# GPS.net
KiCad netlist of a schematic drawn in Altium Designer
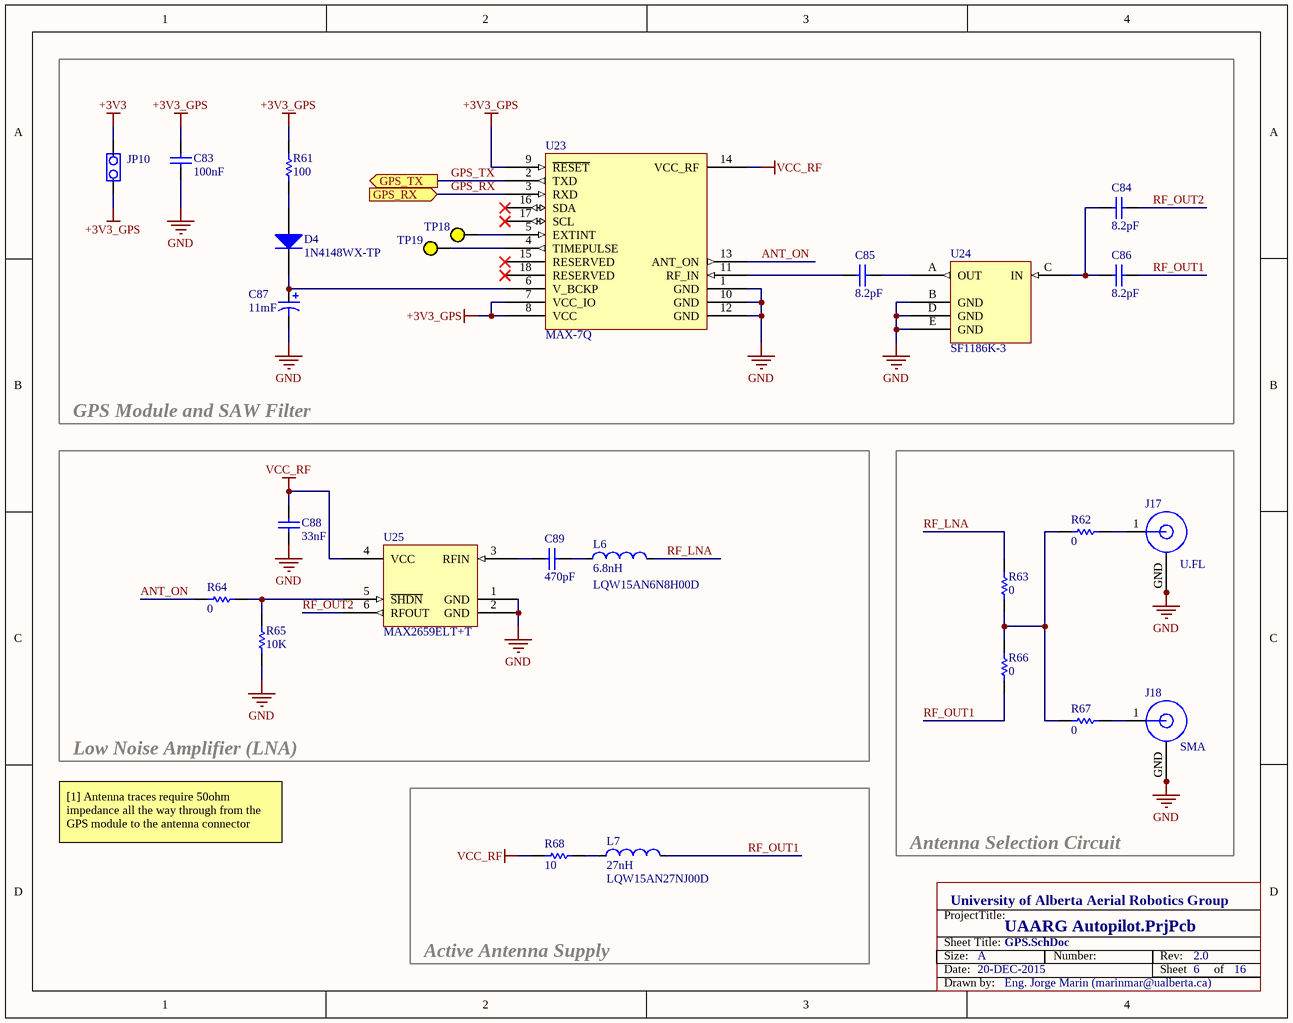
[diagram p0: GPS.SchDoc]

(export (version "E")
  (design (tool "Eeschema 10.0.6"))
  (components
    (comp (ref "C83")
      (value "100nF")
      (footprint "CAP_0402[1005M]")
      (description "Capacitor")
      (fields
        (field (name "MANUFACTURER") "Yageo")
        (field (name "MANUFACTURER PART NUMBER") "CC0402KRX7R6BB104")
      )
      (libsource (lib "UAARG Autopilot") (part "CAP"))
    )
    (comp (ref "C84")
      (value "8.2pF")
      (footprint "CAP_0402[1005M]")
      (description "Capacitor")
      (fields
        (field (name "MANUFACTURER") "Yageo")
        (field (name "MANUFACTURER PART NUMBER") "CC0402BRNPO9BN8R2")
      )
      (libsource (lib "UAARG Autopilot") (part "CAP"))
    )
    (comp (ref "C85")
      (value "8.2pF")
      (footprint "CAP_0402[1005M]")
      (description "Capacitor")
      (fields
        (field (name "MANUFACTURER") "Yageo")
        (field (name "MANUFACTURER PART NUMBER") "CC0402BRNPO9BN8R2")
      )
      (libsource (lib "UAARG Autopilot") (part "CAP"))
    )
    (comp (ref "C86")
      (value "8.2pF")
      (footprint "CAP_0402[1005M]")
      (description "Capacitor")
      (fields
        (field (name "MANUFACTURER") "Yageo")
        (field (name "MANUFACTURER PART NUMBER") "CC0402BRNPO9BN8R2")
      )
      (libsource (lib "UAARG Autopilot") (part "CAP"))
    )
    (comp (ref "C87")
      (value "11mF")
      (footprint "SUPERCAP_1210[3225M]")
      (description "Polarized Capacitor")
      (fields
        (field (name "MANUFACTURER") "Seiko Instruments")
        (field (name "MANUFACTURER PART NUMBER") "CPH3225A")
      )
      (libsource (lib "UAARG Autopilot") (part "CAP_POL"))
    )
    (comp (ref "C88")
      (value "33nF")
      (footprint "CAP_0402[1005M]")
      (description "Capacitor")
      (fields
        (field (name "MANUFACTURER PART NUMBER") "CL05B333JO5NNNC")
        (field (name "MANUFACTURER") "Samsung Electro-Mechanics America, Inc.")
      )
      (libsource (lib "UAARG Autopilot") (part "CAP"))
    )
    (comp (ref "C89")
      (value "470pF")
      (footprint "CAP_0402[1005M]")
      (description "Capacitor")
      (fields
        (field (name "MANUFACTURER PART NUMBER") "C1005C0G1H471J050BA")
        (field (name "MANUFACTURER") "TDK Corporation")
      )
      (libsource (lib "UAARG Autopilot") (part "CAP"))
    )
    (comp (ref "D4")
      (value "DIODE")
      (footprint "SOD-323")
      (description "Typical Diode")
      (fields
        (field (name "MANUFACTURER PART NUMBER") "1N4148WX-TP")
        (field (name "MANUFACTURER") "Micro Commercial Co")
      )
      (libsource (lib "UAARG Autopilot") (part "DIODE"))
    )
    (comp (ref "J17")
      (value "U.FL")
      (footprint "U.FL_1")
      (description "U.FL RF connector")
      (fields
        (field (name "MANUFACTURER") "Hirose Electric Co Ltd")
        (field (name "MANUFACTURER PART NUMBER") "U.FL-R-SMT(10)")
      )
      (libsource (lib "UAARG Autopilot") (part "U.FL"))
    )
    (comp (ref "J18")
      (value "SMA")
      (footprint "SMA")
      (description "SMA RF connector")
      (fields
        (field (name "MANUFACTURER") "Cinch Connectivity Solutions Johnson")
        (field (name "MANUFACTURER PART NUMBER") "142-0701-801")
      )
      (libsource (lib "UAARG Autopilot") (part "U.FL"))
    )
    (comp (ref "JP10")
      (value "Jumper")
      (footprint "HDR_1x02_JMP")
      (libsource (lib "UAARG Autopilot") (part "Jumper"))
    )
    (comp (ref "L6")
      (value "6.8nH")
      (footprint "GEN_0402[1005M]")
      (description "Chip Inductor")
      (fields
        (field (name "MANUFACTURER PART NUMBER") "LQW15AN6N8H00D")
        (field (name "MANUFACTURER") "Murata Electronics North America")
      )
      (libsource (lib "UAARG Autopilot") (part "Inductor"))
    )
    (comp (ref "L7")
      (value "27nH")
      (footprint "GEN_0402[1005M]")
      (description "Chip Inductor")
      (fields
        (field (name "MANUFACTURER") "Murata Electronics North America")
        (field (name "MANUFACTURER PART NUMBER") "LQW15AN27NJ00D")
      )
      (libsource (lib "UAARG Autopilot") (part "Inductor"))
    )
    (comp (ref "R61")
      (value "100")
      (footprint "RES_0402[1005M]")
      (description "Resistor")
      (fields
        (field (name "MANUFACTURER PART NUMBER") "RC0402FR-07100RL")
        (field (name "MANUFACTURER") "Yageo")
      )
      (libsource (lib "UAARG Autopilot") (part "RES"))
    )
    (comp (ref "R62")
      (value "0")
      (footprint "RES_0402[1005M]")
      (description "Resistor")
      (fields
        (field (name "MANUFACTURER PART NUMBER") "RC0402JR-070RL")
        (field (name "MANUFACTURER") "Yageo")
      )
      (libsource (lib "UAARG Autopilot") (part "RES"))
    )
    (comp (ref "R63")
      (value "0")
      (footprint "RES_0402[1005M]")
      (description "Resistor")
      (fields
        (field (name "MANUFACTURER PART NUMBER") "RC0402JR-070RL")
        (field (name "MANUFACTURER") "Yageo")
      )
      (libsource (lib "UAARG Autopilot") (part "RES"))
    )
    (comp (ref "R64")
      (value "0")
      (footprint "RES_0402[1005M]")
      (description "Resistor")
      (fields
        (field (name "MANUFACTURER PART NUMBER") "RC0402JR-070RL")
        (field (name "MANUFACTURER") "Yageo")
      )
      (libsource (lib "UAARG Autopilot") (part "RES"))
    )
    (comp (ref "R65")
      (value "10K")
      (footprint "RES_0402[1005M]")
      (description "Resistor")
      (fields
        (field (name "MANUFACTURER") "Yageo")
        (field (name "MANUFACTURER PART NUMBER") "RC0402FR-0710KL")
      )
      (libsource (lib "UAARG Autopilot") (part "RES"))
    )
    (comp (ref "R66")
      (value "0")
      (footprint "RES_0402[1005M]")
      (description "Resistor")
      (fields
        (field (name "MANUFACTURER PART NUMBER") "RC0402JR-070RL")
        (field (name "MANUFACTURER") "Yageo")
      )
      (libsource (lib "UAARG Autopilot") (part "RES"))
    )
    (comp (ref "R67")
      (value "0")
      (footprint "RES_0402[1005M]")
      (description "Resistor")
      (fields
        (field (name "MANUFACTURER PART NUMBER") "RC0402JR-070RL")
        (field (name "MANUFACTURER") "Yageo")
      )
      (libsource (lib "UAARG Autopilot") (part "RES"))
    )
    (comp (ref "R68")
      (value "10")
      (footprint "RES_0402[1005M]")
      (description "Resistor")
      (fields
        (field (name "MANUFACTURER") "Yageo")
        (field (name "MANUFACTURER PART NUMBER") "RC0402FR-0710RL")
      )
      (libsource (lib "UAARG Autopilot") (part "RES"))
    )
    (comp (ref "TP18")
      (value "Test Point SIG")
      (footprint "TP_SMD_1_SILK")
      (description "Test Point Signal")
      (libsource (lib "UAARG Autopilot") (part "Test Point SIG"))
    )
    (comp (ref "TP19")
      (value "Test Point SIG")
      (footprint "TP_SMD_1_SILK")
      (description "Test Point Signal")
      (libsource (lib "UAARG Autopilot") (part "Test Point SIG"))
    )
    (comp (ref "U23")
      (value "MAX-7Q")
      (footprint "MAX6/7_GPS")
      (description "u-blox MAX-7Q GNSS Module")
      (fields (field (name "MANUFACTURER") "u-blox") (field (name "MANUFACTURER PART NUMBER") "MAX-7Q"))
      (libsource (lib "UAARG Autopilot") (part "MAX-7Q"))
    )
    (comp (ref "U24")
      (value "SF1186K-3")
      (footprint "5-SMD")
      (description "GPS SAW Filter")
      (fields
        (field (name "MANUFACTURER") "Murata Electronics North America")
        (field (name "MANUFACTURER PART NUMBER") "SF1186K-3")
      )
      (libsource (lib "UAARG Autopilot") (part "SF1186K-3"))
    )
    (comp (ref "U25")
      (value "MAX2659ELT+T")
      (footprint "uDFN-6")
      (description "MAX2659 Low Noise Amplifier")
      (fields
        (field (name "MANUFACTURER PART NUMBER") "MAX2659ELT+T")
        (field (name "MANUFACTURER") "Maxim Integrated")
      )
      (libsource (lib "UAARG Autopilot") (part "MAX2659"))
    )
  )
  (nets
    (net (code "1") (name "+3V3") (class "Default")
      (node (ref "JP10") (pin "2") (pinfunction "2_2") (pintype "passive"))
    )
    (net (code "2") (name "+3V3_GPS") (class "Default")
      (node (ref "C83") (pin "2") (pinfunction "2_2") (pintype "passive"))
      (node (ref "JP10") (pin "1") (pinfunction "1_1") (pintype "passive"))
      (node (ref "R61") (pin "1") (pinfunction "1_1") (pintype "passive"))
      (node (ref "U23") (pin "7") (pinfunction "VCC_IO_7") (pintype "power_in"))
      (node (ref "U23") (pin "8") (pinfunction "VCC_8") (pintype "power_in"))
      (node (ref "U23") (pin "9") (pinfunction "~{RESET}_9") (pintype "input"))
    )
    (net (code "3") (name "/ANT_ON") (class "Default")
      (node (ref "R64") (pin "1") (pinfunction "1_1") (pintype "passive"))
      (node (ref "U23") (pin "13") (pinfunction "ANT_ON_13") (pintype "output"))
    )
    (net (code "4") (name "/GPS_RX") (class "Default")
      (node (ref "U23") (pin "3") (pinfunction "RXD_3") (pintype "input"))
    )
    (net (code "5") (name "/GPS_TX") (class "Default")
      (node (ref "U23") (pin "2") (pinfunction "TXD_2") (pintype "output"))
    )
    (net (code "6") (name "/RF_LNA") (class "Default")
      (node (ref "L6") (pin "2") (pinfunction "2_2") (pintype "passive"))
      (node (ref "R63") (pin "2") (pinfunction "2_2") (pintype "passive"))
    )
    (net (code "7") (name "/RF_OUT1") (class "Default")
      (node (ref "C86") (pin "1") (pinfunction "1_1") (pintype "passive"))
      (node (ref "L7") (pin "2") (pinfunction "2_2") (pintype "passive"))
      (node (ref "R66") (pin "1") (pinfunction "1_1") (pintype "passive"))
    )
    (net (code "8") (name "/RF_OUT2") (class "Default")
      (node (ref "C84") (pin "1") (pinfunction "1_1") (pintype "passive"))
      (node (ref "U25") (pin "6") (pinfunction "RFOUT_6") (pintype "output"))
    )
    (net (code "9") (name "GND") (class "Default")
      (node (ref "C83") (pin "1") (pinfunction "1_1") (pintype "passive"))
      (node (ref "C87") (pin "2") (pinfunction "2_2") (pintype "passive"))
      (node (ref "C88") (pin "2") (pinfunction "2_2") (pintype "passive"))
      (node (ref "J17") (pin "GND") (pinfunction "GND_GND") (pintype "passive"))
      (node (ref "J18") (pin "GND") (pinfunction "GND_GND") (pintype "passive"))
      (node (ref "R65") (pin "1") (pinfunction "1_1") (pintype "passive"))
      (node (ref "U23") (pin "1") (pinfunction "GND_1") (pintype "power_in"))
      (node (ref "U23") (pin "10") (pinfunction "GND_10") (pintype "power_in"))
      (node (ref "U23") (pin "12") (pinfunction "GND_12") (pintype "power_in"))
      (node (ref "U24") (pin "B") (pinfunction "GND_B") (pintype "power_in"))
      (node (ref "U24") (pin "D") (pinfunction "GND_D") (pintype "power_in"))
      (node (ref "U24") (pin "E") (pinfunction "GND_E") (pintype "power_in"))
      (node (ref "U25") (pin "1") (pinfunction "GND_1") (pintype "power_in"))
      (node (ref "U25") (pin "2") (pinfunction "GND_2") (pintype "power_in"))
    )
    (net (code "10") (name "Net-(C89-Pad1)") (class "Default")
      (node (ref "C89") (pin "1") (pinfunction "1_1") (pintype "passive"))
      (node (ref "L6") (pin "1") (pinfunction "1_1") (pintype "passive"))
    )
    (net (code "11") (name "Net-(D4-A)") (class "Default")
      (node (ref "D4") (pin "1") (pinfunction "A_1") (pintype "passive"))
      (node (ref "R61") (pin "2") (pinfunction "2_2") (pintype "passive"))
    )
    (net (code "12") (name "Net-(D4-K)") (class "Default")
      (node (ref "C87") (pin "1") (pinfunction "1_1") (pintype "passive"))
      (node (ref "D4") (pin "2") (pinfunction "K_2") (pintype "passive"))
      (node (ref "U23") (pin "6") (pinfunction "V_BCKP_6") (pintype "power_in"))
    )
    (net (code "13") (name "Net-(J17-OSC1)") (class "Default")
      (node (ref "J17") (pin "1") (pinfunction "OSC1_1") (pintype "passive"))
      (node (ref "R62") (pin "1") (pinfunction "1_1") (pintype "passive"))
    )
    (net (code "14") (name "Net-(J18-OSC1)") (class "Default")
      (node (ref "J18") (pin "1") (pinfunction "OSC1_1") (pintype "passive"))
      (node (ref "R67") (pin "1") (pinfunction "1_1") (pintype "passive"))
    )
    (net (code "15") (name "Net-(L7-Pad1)") (class "Default")
      (node (ref "L7") (pin "1") (pinfunction "1_1") (pintype "passive"))
      (node (ref "R68") (pin "2") (pinfunction "2_2") (pintype "passive"))
    )
    (net (code "16") (name "Net-(R62-Pad2)") (class "Default")
      (node (ref "R62") (pin "2") (pinfunction "2_2") (pintype "passive"))
      (node (ref "R63") (pin "1") (pinfunction "1_1") (pintype "passive"))
      (node (ref "R66") (pin "2") (pinfunction "2_2") (pintype "passive"))
      (node (ref "R67") (pin "2") (pinfunction "2_2") (pintype "passive"))
    )
    (net (code "17") (name "Net-(U23-EXTINT)") (class "Default")
      (node (ref "TP18") (pin "1") (pinfunction "1_1") (pintype "passive"))
      (node (ref "U23") (pin "5") (pinfunction "EXTINT_5") (pintype "input"))
    )
    (net (code "18") (name "Net-(U23-RF_IN)") (class "Default")
      (node (ref "C85") (pin "2") (pinfunction "2_2") (pintype "passive"))
      (node (ref "U23") (pin "11") (pinfunction "RF_IN_11") (pintype "input"))
    )
    (net (code "19") (name "Net-(U23-TIMEPULSE)") (class "Default")
      (node (ref "TP19") (pin "1") (pinfunction "1_1") (pintype "passive"))
      (node (ref "U23") (pin "4") (pinfunction "TIMEPULSE_4") (pintype "output"))
    )
    (net (code "20") (name "Net-(U24-IN)") (class "Default")
      (node (ref "C84") (pin "2") (pinfunction "2_2") (pintype "passive"))
      (node (ref "C86") (pin "2") (pinfunction "2_2") (pintype "passive"))
      (node (ref "U24") (pin "C") (pinfunction "IN_C") (pintype "input"))
    )
    (net (code "21") (name "Net-(U24-OUT)") (class "Default")
      (node (ref "C85") (pin "1") (pinfunction "1_1") (pintype "passive"))
      (node (ref "U24") (pin "A") (pinfunction "OUT_A") (pintype "output"))
    )
    (net (code "22") (name "Net-(U25-RFIN)") (class "Default")
      (node (ref "C89") (pin "2") (pinfunction "2_2") (pintype "passive"))
      (node (ref "U25") (pin "3") (pinfunction "RFIN_3") (pintype "input"))
    )
    (net (code "23") (name "Net-(U25-~{SHDN})") (class "Default")
      (node (ref "R64") (pin "2") (pinfunction "2_2") (pintype "passive"))
      (node (ref "R65") (pin "2") (pinfunction "2_2") (pintype "passive"))
      (node (ref "U25") (pin "5") (pinfunction "~{SHDN}_5") (pintype "input"))
    )
    (net (code "24") (name "VCC_RF") (class "Default")
      (node (ref "C88") (pin "1") (pinfunction "1_1") (pintype "passive"))
      (node (ref "R68") (pin "1") (pinfunction "1_1") (pintype "passive"))
      (node (ref "U23") (pin "14") (pinfunction "VCC_RF_14") (pintype "power_in"))
      (node (ref "U25") (pin "4") (pinfunction "VCC_4") (pintype "power_in"))
    )
    (net (code "25") (name "unconnected-(U23-RESERVED-Pad15)") (class "Default")
      (node (ref "U23") (pin "15") (pinfunction "RESERVED_15") (pintype "passive+no_connect"))
    )
    (net (code "26") (name "unconnected-(U23-RESERVED-Pad18)") (class "Default")
      (node (ref "U23") (pin "18") (pinfunction "RESERVED_18") (pintype "passive+no_connect"))
    )
    (net (code "27") (name "unconnected-(U23-SCL-Pad17)") (class "Default")
      (node (ref "U23") (pin "17") (pinfunction "SCL_17") (pintype "bidirectional+no_connect"))
    )
    (net (code "28") (name "unconnected-(U23-SDA-Pad16)") (class "Default")
      (node (ref "U23") (pin "16") (pinfunction "SDA_16") (pintype "bidirectional+no_connect"))
    )
  )
)
